# Advanced_IMU.net
KiCad netlist of a schematic drawn in EAGLE
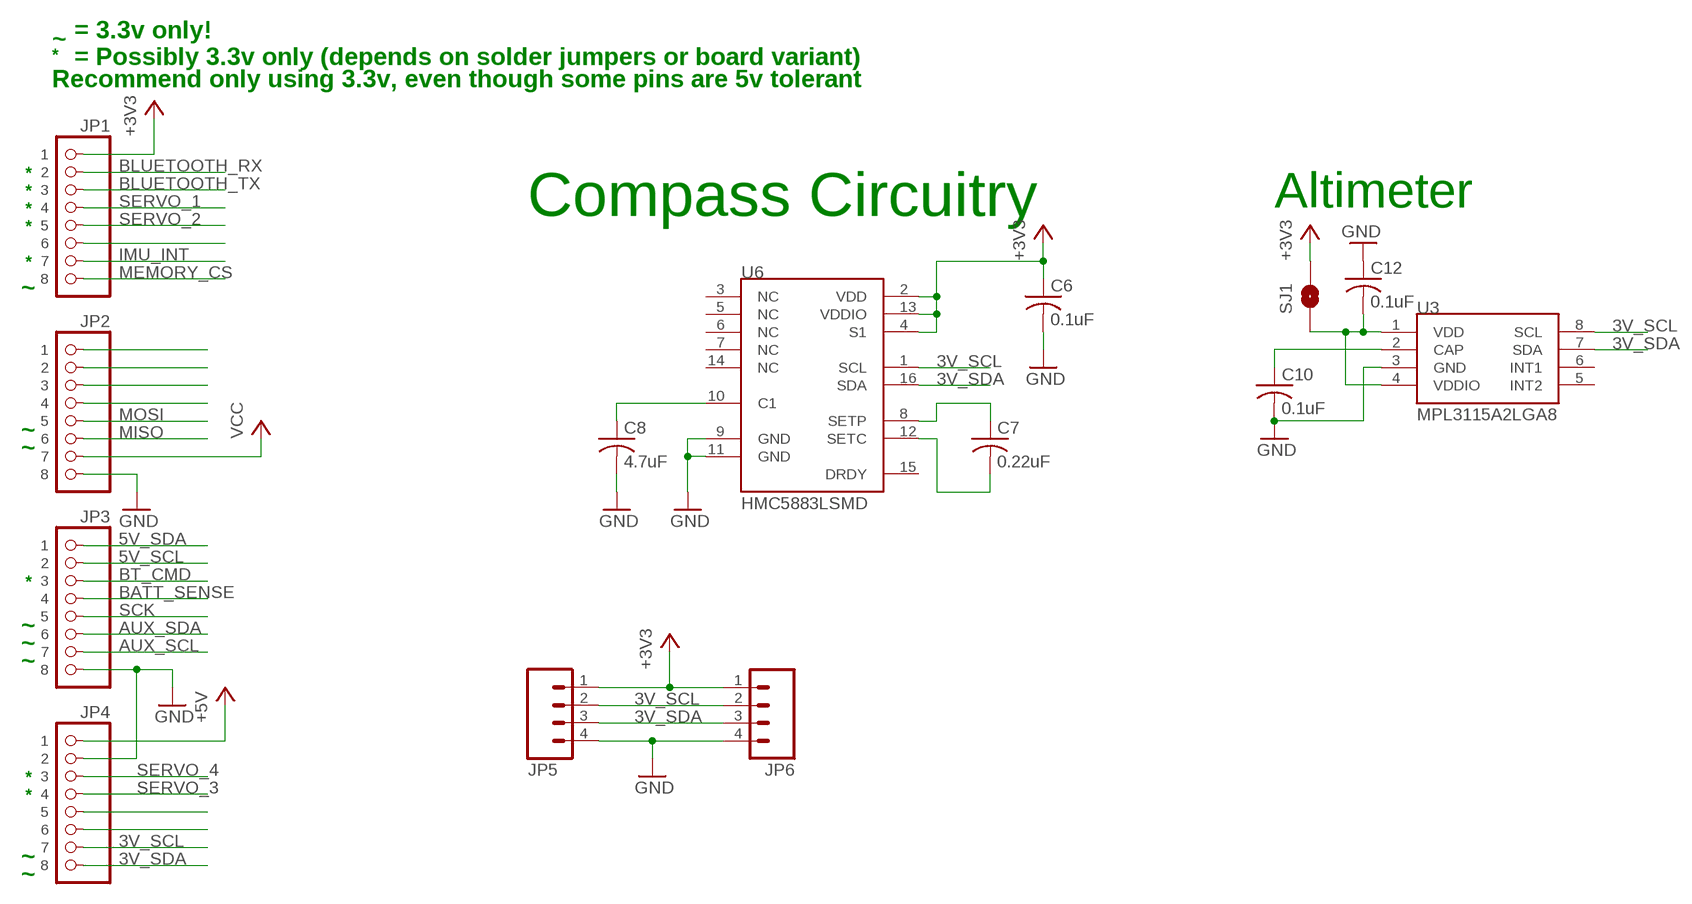
[diagram p0: schematic, sheet 1]

(export (version "E")
  (design (tool "Eeschema 10.0.6"))
  (components
    (comp (ref "C6")
      (value "0.1uF")
      (footprint "eagle-import:C0603")
      (libsource (lib "eagle-import") (part "C-USC0603"))
    )
    (comp (ref "C7")
      (value "0.22uF")
      (footprint "eagle-import:C0603")
      (libsource (lib "eagle-import") (part "C-USC0603"))
    )
    (comp (ref "C8")
      (value "4.7uF")
      (footprint "eagle-import:C0603")
      (libsource (lib "eagle-import") (part "C-USC0603"))
    )
    (comp (ref "C10")
      (value "0.1uF")
      (footprint "eagle-import:C0603")
      (libsource (lib "eagle-import") (part "C-USC0603"))
    )
    (comp (ref "C12")
      (value "0.1uF")
      (footprint "eagle-import:C0603")
      (libsource (lib "eagle-import") (part "C-USC0603"))
    )
    (comp (ref "JP1")
      (value "8-PIN_HEADER")
      (footprint "eagle-import:8-PIN_RECEPTACLE_LOCK_NO-SS")
      (libsource (lib "eagle-import") (part "8-PIN_HEADER"))
    )
    (comp (ref "JP2")
      (value "8-PIN_HEADER")
      (footprint "eagle-import:8-PIN_RECEPTACLE_LOCK_NO-SS")
      (libsource (lib "eagle-import") (part "8-PIN_HEADER"))
    )
    (comp (ref "JP3")
      (value "8-PIN_HEADER")
      (footprint "eagle-import:8-PIN_RECEPTACLE_LOCK_NO-SS")
      (libsource (lib "eagle-import") (part "8-PIN_HEADER"))
    )
    (comp (ref "JP4")
      (value "8-PIN_HEADER")
      (footprint "eagle-import:8-PIN_RECEPTACLE_LOCK_NO-SS")
      (libsource (lib "eagle-import") (part "8-PIN_HEADER"))
    )
    (comp (ref "JP5")
      (value "M04PTH")
      (footprint "eagle-import:1X04")
      (libsource (lib "eagle-import") (part "M04PTH"))
    )
    (comp (ref "JP6")
      (value "M04PTH")
      (footprint "eagle-import:1X04")
      (libsource (lib "eagle-import") (part "M04PTH"))
    )
    (comp (ref "SJ1")
      (value "SOLDERJUMPERNC")
      (footprint "eagle-import:SJ_2S")
      (libsource (lib "eagle-import") (part "SOLDERJUMPERNC"))
    )
    (comp (ref "U3")
      (value "MPL3115A2LGA8")
      (footprint "eagle-import:LGA8")
      (libsource (lib "eagle-import") (part "MPL3115A2LGA8"))
    )
    (comp (ref "U6")
      (value "HMC5883LSMD")
      (footprint "eagle-import:16LPCC")
      (libsource (lib "eagle-import") (part "HMC5883LSMD"))
    )
  )
  (nets
    (net (code "1") (name "+3V3") (class "Default")
      (node (ref "C6") (pin "1") (pinfunction "1_1") (pintype "passive"))
      (node (ref "JP1") (pin "P$1") (pinfunction "1_P$1") (pintype "passive"))
      (node (ref "JP5") (pin "1") (pinfunction "1_1") (pintype "passive"))
      (node (ref "JP6") (pin "1") (pinfunction "1_1") (pintype "passive"))
      (node (ref "SJ1") (pin "2") (pinfunction "2_2") (pintype "passive"))
      (node (ref "U6") (pin "13") (pinfunction "VDDIO_13") (pintype "bidirectional"))
      (node (ref "U6") (pin "2") (pinfunction "VDD_2") (pintype "bidirectional"))
      (node (ref "U6") (pin "4") (pinfunction "S1_4") (pintype "bidirectional"))
    )
    (net (code "2") (name "+5V") (class "Default")
      (node (ref "JP4") (pin "P$1") (pinfunction "1_P$1") (pintype "passive"))
    )
    (net (code "3") (name "/3V_SCL") (class "Default")
      (node (ref "JP4") (pin "P$7") (pinfunction "7_P$7") (pintype "passive"))
      (node (ref "JP5") (pin "2") (pinfunction "2_2") (pintype "passive"))
      (node (ref "JP6") (pin "2") (pinfunction "2_2") (pintype "passive"))
      (node (ref "U3") (pin "8") (pinfunction "SCL_8") (pintype "bidirectional"))
      (node (ref "U6") (pin "1") (pinfunction "SCL_1") (pintype "bidirectional"))
    )
    (net (code "4") (name "/3V_SDA") (class "Default")
      (node (ref "JP4") (pin "P$8") (pinfunction "8_P$8") (pintype "passive"))
      (node (ref "JP5") (pin "3") (pinfunction "3_3") (pintype "passive"))
      (node (ref "JP6") (pin "3") (pinfunction "3_3") (pintype "passive"))
      (node (ref "U3") (pin "7") (pinfunction "SDA_7") (pintype "bidirectional"))
      (node (ref "U6") (pin "16") (pinfunction "SDA_16") (pintype "bidirectional"))
    )
    (net (code "5") (name "/5V_SCL") (class "Default")
      (node (ref "JP3") (pin "P$2") (pinfunction "2_P$2") (pintype "passive"))
    )
    (net (code "6") (name "/5V_SDA") (class "Default")
      (node (ref "JP3") (pin "P$1") (pinfunction "1_P$1") (pintype "passive"))
    )
    (net (code "7") (name "/AUX_SCL") (class "Default")
      (node (ref "JP3") (pin "P$7") (pinfunction "7_P$7") (pintype "passive"))
    )
    (net (code "8") (name "/AUX_SDA") (class "Default")
      (node (ref "JP3") (pin "P$6") (pinfunction "6_P$6") (pintype "passive"))
    )
    (net (code "9") (name "/BATT_SENSE") (class "Default")
      (node (ref "JP3") (pin "P$4") (pinfunction "4_P$4") (pintype "passive"))
    )
    (net (code "10") (name "/BLUETOOTH_RX") (class "Default")
      (node (ref "JP1") (pin "P$2") (pinfunction "2_P$2") (pintype "passive"))
    )
    (net (code "11") (name "/BLUETOOTH_TX") (class "Default")
      (node (ref "JP1") (pin "P$3") (pinfunction "3_P$3") (pintype "passive"))
    )
    (net (code "12") (name "/BT_CMD") (class "Default")
      (node (ref "JP3") (pin "P$3") (pinfunction "3_P$3") (pintype "passive"))
    )
    (net (code "13") (name "/IMU_INT") (class "Default")
      (node (ref "JP1") (pin "P$7") (pinfunction "7_P$7") (pintype "passive"))
    )
    (net (code "14") (name "/MEMORY_CS") (class "Default")
      (node (ref "JP1") (pin "P$8") (pinfunction "8_P$8") (pintype "passive"))
    )
    (net (code "15") (name "/MISO") (class "Default")
      (node (ref "JP2") (pin "P$6") (pinfunction "6_P$6") (pintype "passive"))
    )
    (net (code "16") (name "/MOSI") (class "Default")
      (node (ref "JP2") (pin "P$5") (pinfunction "5_P$5") (pintype "passive"))
    )
    (net (code "17") (name "/SCK") (class "Default")
      (node (ref "JP3") (pin "P$5") (pinfunction "5_P$5") (pintype "passive"))
    )
    (net (code "18") (name "/SERVO_1") (class "Default")
      (node (ref "JP1") (pin "P$4") (pinfunction "4_P$4") (pintype "passive"))
    )
    (net (code "19") (name "/SERVO_2") (class "Default")
      (node (ref "JP1") (pin "P$5") (pinfunction "5_P$5") (pintype "passive"))
    )
    (net (code "20") (name "/SERVO_3") (class "Default")
      (node (ref "JP4") (pin "P$4") (pinfunction "4_P$4") (pintype "passive"))
    )
    (net (code "21") (name "/SERVO_4") (class "Default")
      (node (ref "JP4") (pin "P$3") (pinfunction "3_P$3") (pintype "passive"))
    )
    (net (code "22") (name "GND") (class "Default")
      (node (ref "C10") (pin "2") (pinfunction "2_2") (pintype "passive"))
      (node (ref "C12") (pin "1") (pinfunction "1_1") (pintype "passive"))
      (node (ref "C6") (pin "2") (pinfunction "2_2") (pintype "passive"))
      (node (ref "C8") (pin "2") (pinfunction "2_2") (pintype "passive"))
      (node (ref "JP2") (pin "P$8") (pinfunction "8_P$8") (pintype "passive"))
      (node (ref "JP3") (pin "P$8") (pinfunction "8_P$8") (pintype "passive"))
      (node (ref "JP4") (pin "P$2") (pinfunction "2_P$2") (pintype "passive"))
      (node (ref "JP5") (pin "4") (pinfunction "4_4") (pintype "passive"))
      (node (ref "JP6") (pin "4") (pinfunction "4_4") (pintype "passive"))
      (node (ref "U3") (pin "3") (pinfunction "GND_3") (pintype "bidirectional"))
      (node (ref "U6") (pin "11") (pinfunction "GND_11") (pintype "bidirectional"))
      (node (ref "U6") (pin "9") (pinfunction "GND_9") (pintype "bidirectional"))
    )
    (net (code "23") (name "Net-(U3-CAP)") (class "Default")
      (node (ref "C10") (pin "1") (pinfunction "1_1") (pintype "passive"))
      (node (ref "U3") (pin "2") (pinfunction "CAP_2") (pintype "bidirectional"))
    )
    (net (code "24") (name "Net-(U3-VDD)") (class "Default")
      (node (ref "C12") (pin "2") (pinfunction "2_2") (pintype "passive"))
      (node (ref "SJ1") (pin "1") (pinfunction "1_1") (pintype "passive"))
      (node (ref "U3") (pin "1") (pinfunction "VDD_1") (pintype "bidirectional"))
      (node (ref "U3") (pin "4") (pinfunction "VDDIO_4") (pintype "bidirectional"))
    )
    (net (code "25") (name "Net-(U6-C1)") (class "Default")
      (node (ref "C8") (pin "1") (pinfunction "1_1") (pintype "passive"))
      (node (ref "U6") (pin "10") (pinfunction "C1_10") (pintype "bidirectional"))
    )
    (net (code "26") (name "Net-(U6-SETC)") (class "Default")
      (node (ref "C7") (pin "2") (pinfunction "2_2") (pintype "passive"))
      (node (ref "U6") (pin "12") (pinfunction "SETC_12") (pintype "bidirectional"))
    )
    (net (code "27") (name "Net-(U6-SETP)") (class "Default")
      (node (ref "C7") (pin "1") (pinfunction "1_1") (pintype "passive"))
      (node (ref "U6") (pin "8") (pinfunction "SETP_8") (pintype "bidirectional"))
    )
    (net (code "28") (name "VCC") (class "Default")
      (node (ref "JP2") (pin "P$7") (pinfunction "7_P$7") (pintype "passive"))
    )
    (net (code "29") (name "unconnected-(JP1-6-PadP$6)") (class "Default")
      (node (ref "JP1") (pin "P$6") (pinfunction "6_P$6") (pintype "passive"))
    )
    (net (code "30") (name "unconnected-(JP2-1-PadP$1)") (class "Default")
      (node (ref "JP2") (pin "P$1") (pinfunction "1_P$1") (pintype "passive"))
    )
    (net (code "31") (name "unconnected-(JP2-2-PadP$2)") (class "Default")
      (node (ref "JP2") (pin "P$2") (pinfunction "2_P$2") (pintype "passive"))
    )
    (net (code "32") (name "unconnected-(JP2-3-PadP$3)") (class "Default")
      (node (ref "JP2") (pin "P$3") (pinfunction "3_P$3") (pintype "passive"))
    )
    (net (code "33") (name "unconnected-(JP2-4-PadP$4)") (class "Default")
      (node (ref "JP2") (pin "P$4") (pinfunction "4_P$4") (pintype "passive"))
    )
    (net (code "34") (name "unconnected-(JP4-5-PadP$5)") (class "Default")
      (node (ref "JP4") (pin "P$5") (pinfunction "5_P$5") (pintype "passive"))
    )
    (net (code "35") (name "unconnected-(JP4-6-PadP$6)") (class "Default")
      (node (ref "JP4") (pin "P$6") (pinfunction "6_P$6") (pintype "passive"))
    )
    (net (code "36") (name "unconnected-(U3-INT1-Pad6)") (class "Default")
      (node (ref "U3") (pin "6") (pinfunction "INT1_6") (pintype "bidirectional"))
    )
    (net (code "37") (name "unconnected-(U3-INT2-Pad5)") (class "Default")
      (node (ref "U3") (pin "5") (pinfunction "INT2_5") (pintype "bidirectional"))
    )
    (net (code "38") (name "unconnected-(U6-DRDY-Pad15)") (class "Default")
      (node (ref "U6") (pin "15") (pinfunction "DRDY_15") (pintype "bidirectional"))
    )
    (net (code "39") (name "unconnected-(U6-NC-Pad3)") (class "Default")
      (node (ref "U6") (pin "3") (pinfunction "NC_3") (pintype "bidirectional"))
    )
    (net (code "40") (name "unconnected-(U6-NC-Pad5)") (class "Default")
      (node (ref "U6") (pin "5") (pinfunction "NC_5") (pintype "bidirectional"))
    )
    (net (code "41") (name "unconnected-(U6-NC-Pad6)") (class "Default")
      (node (ref "U6") (pin "6") (pinfunction "NC_6") (pintype "bidirectional"))
    )
    (net (code "42") (name "unconnected-(U6-NC-Pad7)") (class "Default")
      (node (ref "U6") (pin "7") (pinfunction "NC_7") (pintype "bidirectional"))
    )
    (net (code "43") (name "unconnected-(U6-NC-Pad14)") (class "Default")
      (node (ref "U6") (pin "14") (pinfunction "NC_14") (pintype "bidirectional"))
    )
  )
)
